# breathing_LED.net
KiCad netlist of a schematic drawn in EasyEDA
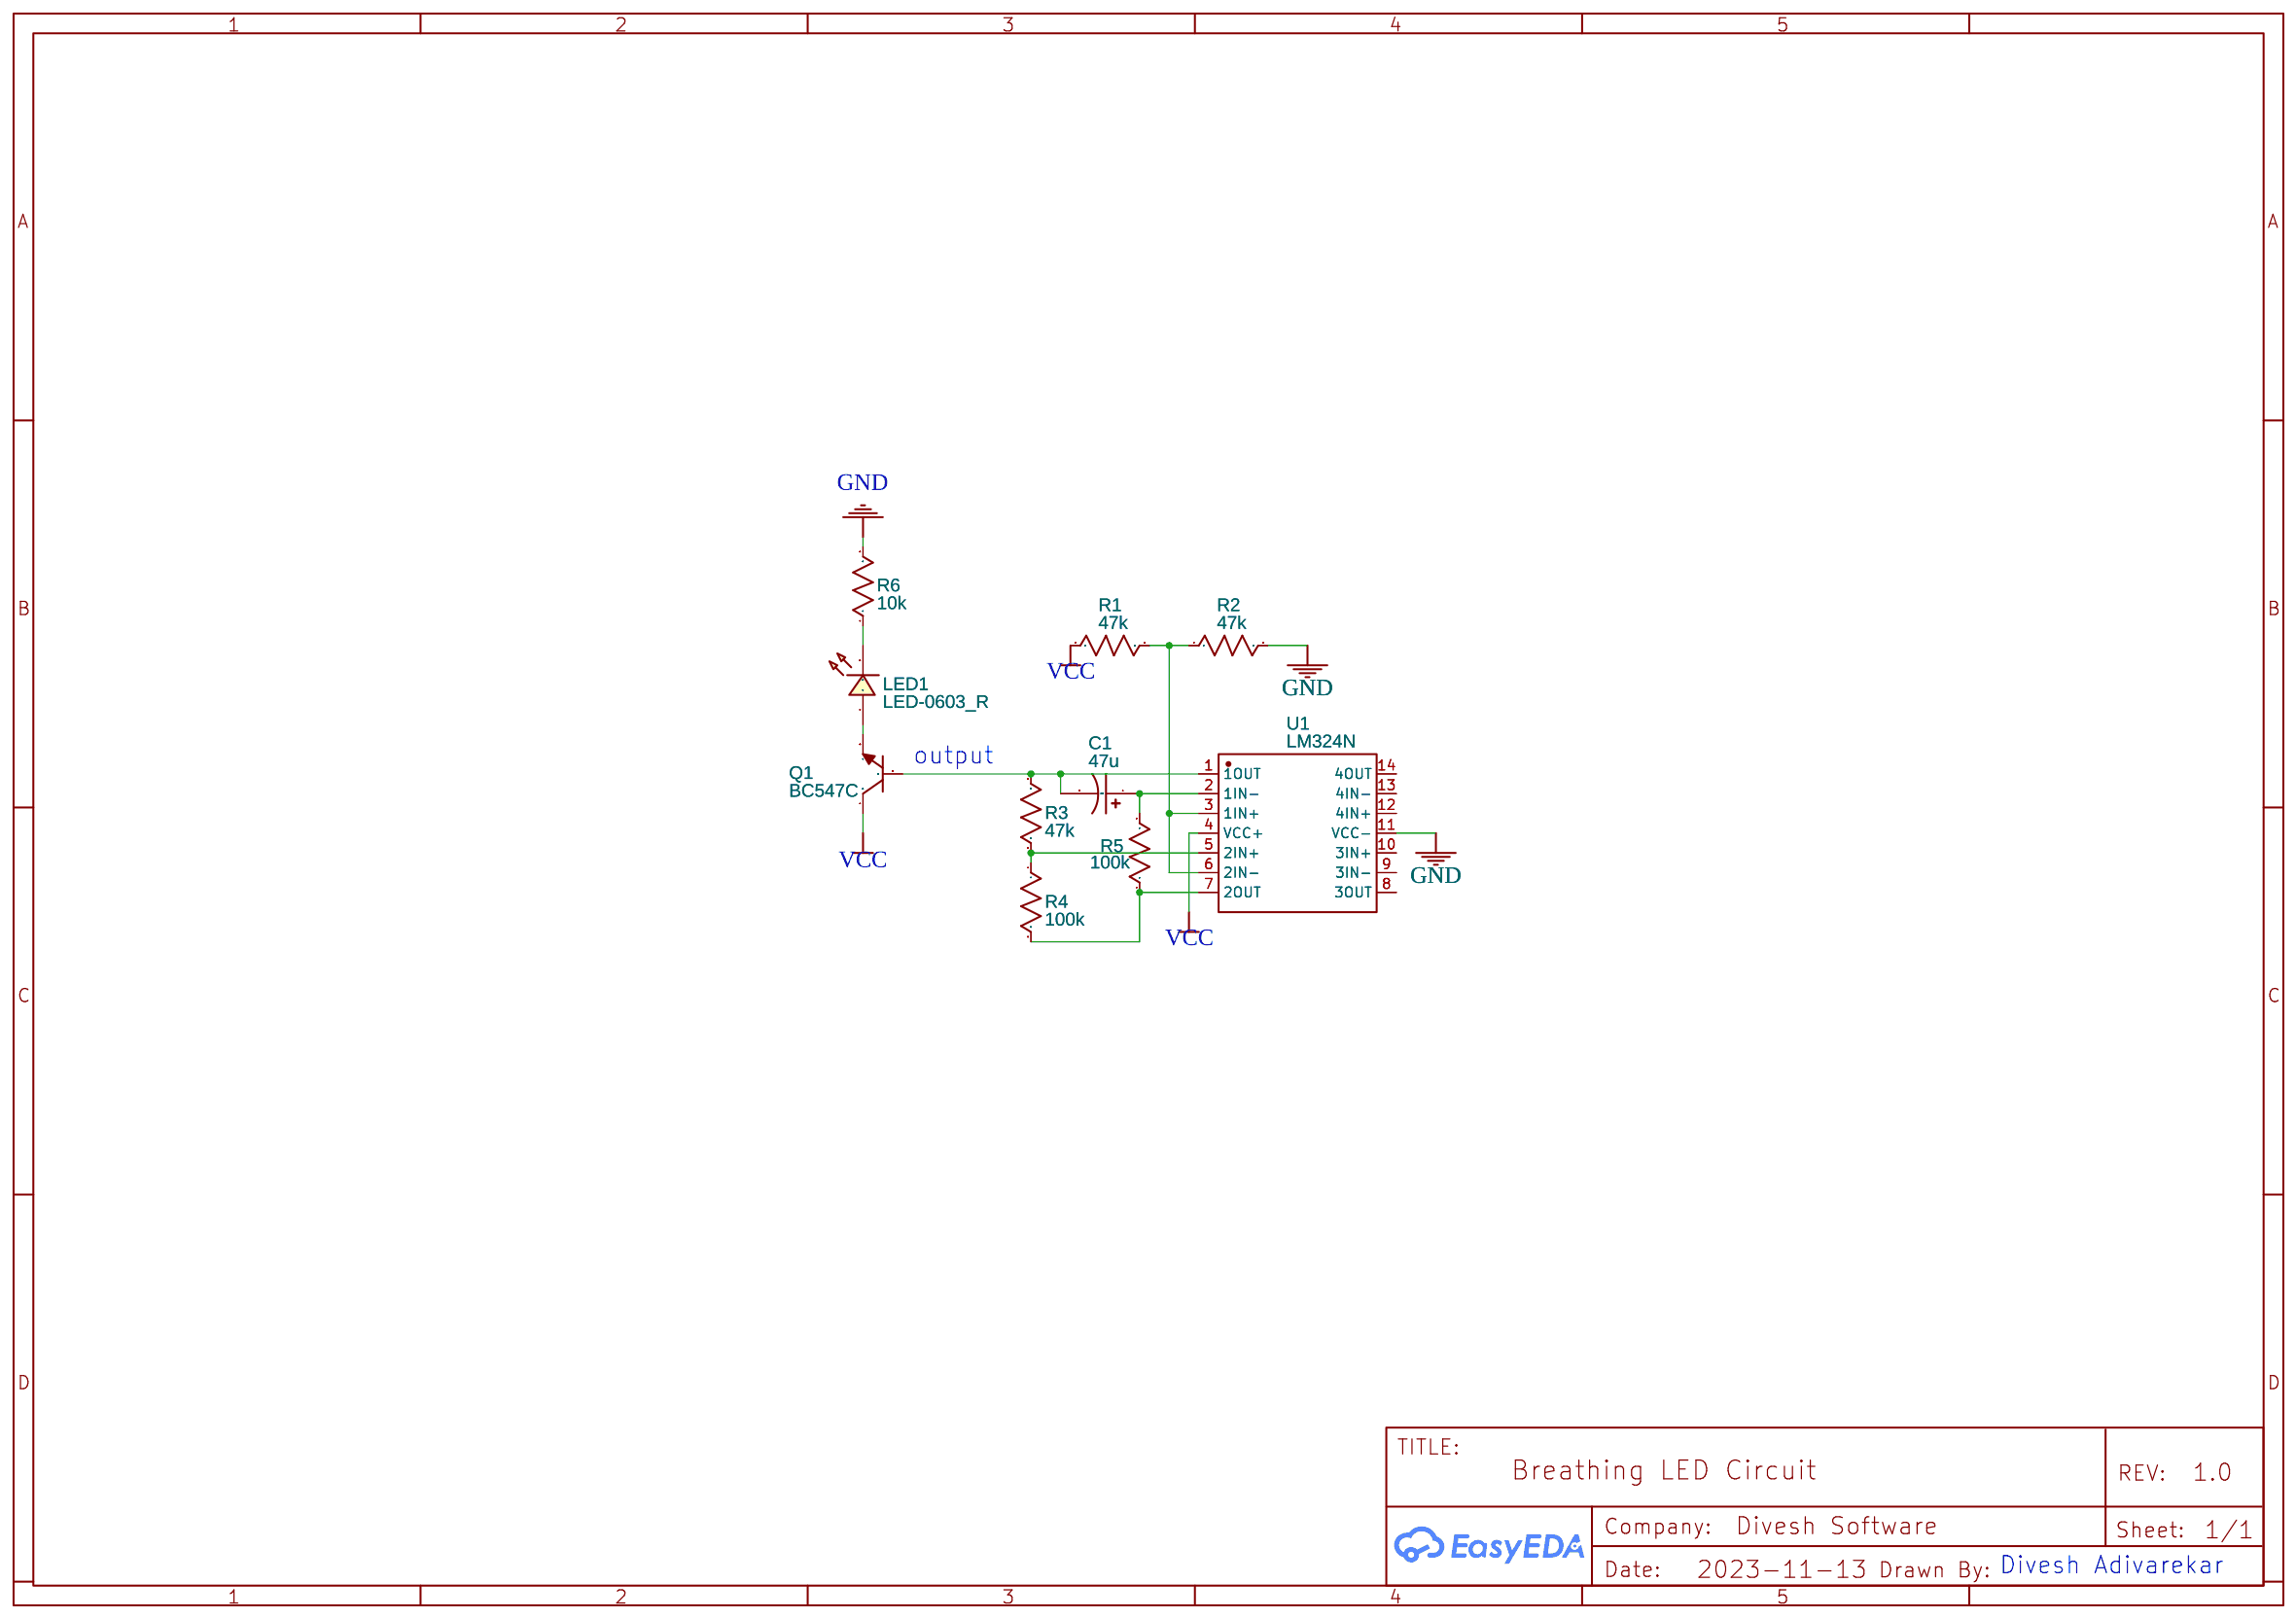
[diagram p0: schematic sheet]

(export (version "E")
  (design (tool "Eeschema 10.0.6"))
  (components
    (comp (ref "C1") (value "47u") (libsource (lib "") (part "C_Tan_SMD_A_US")))
    (comp (ref "LED1")
      (value "LED-0603_R")
      (fields
        (field (name "Manufacturer Part") "19-217/R6C-AL1M2VY/3T")
        (field (name "Manufacturer") "EVERLIGHT(台湾亿光)")
      )
      (libsource (lib "") (part "LED-0603_R"))
    )
    (comp (ref "Q1")
      (value "BC547C")
      (fields (field (name "Manufacturer") "LGE(鲁光)"))
      (libsource (lib "") (part "BC547C"))
    )
    (comp (ref "R1") (value "47k") (libsource (lib "") (part "R_0603_US_1")))
    (comp (ref "R2") (value "47k") (libsource (lib "") (part "R_0603_US_1")))
    (comp (ref "R3") (value "47k") (libsource (lib "") (part "R_0603_US_2")))
    (comp (ref "R4") (value "100k") (libsource (lib "") (part "R_0603_US")))
    (comp (ref "R5") (value "100k") (libsource (lib "") (part "R_0603_US_2")))
    (comp (ref "R6") (value "10k") (libsource (lib "") (part "R_0603_US_2")))
    (comp (ref "U1")
      (value "LM324N")
      (fields (field (name "Manufacturer") "TI(德州仪器)"))
      (libsource (lib "") (part "LM324N"))
    )
  )
  (nets
    (net (code "1") (name "GND") (class "Default")
      (node (ref "R2") (pin "2") (pinfunction "2_2") (pintype "unspecified"))
      (node (ref "R6") (pin "2") (pinfunction "2_2") (pintype "unspecified"))
      (node (ref "U1") (pin "11") (pinfunction "VCC-_11") (pintype "unspecified"))
    )
    (net (code "2") (name "Net-(LED1-Pad2)") (class "Default")
      (node (ref "LED1") (pin "2") (pinfunction "2_2") (pintype "unspecified"))
      (node (ref "R6") (pin "1") (pinfunction "1_1") (pintype "unspecified"))
    )
    (net (code "3") (name "Net-(Q1-B)") (class "Default")
      (node (ref "C1") (pin "2") (pinfunction "2_2") (pintype "unspecified"))
      (node (ref "Q1") (pin "2") (pinfunction "B_2") (pintype "input"))
      (node (ref "R3") (pin "2") (pinfunction "2_2") (pintype "unspecified"))
      (node (ref "U1") (pin "1") (pinfunction "1OUT_1") (pintype "unspecified"))
    )
    (net (code "4") (name "Net-(Q1-E)") (class "Default")
      (node (ref "LED1") (pin "1") (pinfunction "1_1") (pintype "unspecified"))
      (node (ref "Q1") (pin "3") (pinfunction "E_3") (pintype "input"))
    )
    (net (code "5") (name "Net-(U1-1IN+)") (class "Default")
      (node (ref "R1") (pin "2") (pinfunction "2_2") (pintype "unspecified"))
      (node (ref "R2") (pin "1") (pinfunction "1_1") (pintype "unspecified"))
      (node (ref "U1") (pin "3") (pinfunction "1IN+_3") (pintype "unspecified"))
      (node (ref "U1") (pin "6") (pinfunction "2IN-_6") (pintype "unspecified"))
    )
    (net (code "6") (name "Net-(U1-1IN-)") (class "Default")
      (node (ref "C1") (pin "1") (pinfunction "1_1") (pintype "unspecified"))
      (node (ref "R5") (pin "2") (pinfunction "2_2") (pintype "unspecified"))
      (node (ref "U1") (pin "2") (pinfunction "1IN-_2") (pintype "unspecified"))
    )
    (net (code "7") (name "Net-(U1-2IN+)") (class "Default")
      (node (ref "R3") (pin "1") (pinfunction "1_1") (pintype "unspecified"))
      (node (ref "R4") (pin "1") (pinfunction "1_1") (pintype "unspecified"))
      (node (ref "U1") (pin "5") (pinfunction "2IN+_5") (pintype "unspecified"))
    )
    (net (code "8") (name "Net-(U1-2OUT)") (class "Default")
      (node (ref "R4") (pin "2") (pinfunction "2_2") (pintype "unspecified"))
      (node (ref "R5") (pin "1") (pinfunction "1_1") (pintype "unspecified"))
      (node (ref "U1") (pin "7") (pinfunction "2OUT_7") (pintype "unspecified"))
    )
    (net (code "9") (name "VCC") (class "Default")
      (node (ref "Q1") (pin "1") (pinfunction "C_1") (pintype "input"))
      (node (ref "R1") (pin "1") (pinfunction "1_1") (pintype "unspecified"))
      (node (ref "U1") (pin "4") (pinfunction "VCC+_4") (pintype "unspecified"))
    )
    (net (code "10") (name "unconnected-(U1-3IN+-Pad10)") (class "Default")
      (node (ref "U1") (pin "10") (pinfunction "3IN+_10") (pintype "unspecified"))
    )
    (net (code "11") (name "unconnected-(U1-3IN--Pad9)") (class "Default")
      (node (ref "U1") (pin "9") (pinfunction "3IN-_9") (pintype "unspecified"))
    )
    (net (code "12") (name "unconnected-(U1-3OUT-Pad8)") (class "Default")
      (node (ref "U1") (pin "8") (pinfunction "3OUT_8") (pintype "unspecified"))
    )
    (net (code "13") (name "unconnected-(U1-4IN+-Pad12)") (class "Default")
      (node (ref "U1") (pin "12") (pinfunction "4IN+_12") (pintype "unspecified"))
    )
    (net (code "14") (name "unconnected-(U1-4IN--Pad13)") (class "Default")
      (node (ref "U1") (pin "13") (pinfunction "4IN-_13") (pintype "unspecified"))
    )
    (net (code "15") (name "unconnected-(U1-4OUT-Pad14)") (class "Default")
      (node (ref "U1") (pin "14") (pinfunction "4OUT_14") (pintype "unspecified"))
    )
  )
)
